# tube-inner_sch-pcb.net
KiCad netlist of a schematic drawn in EAGLE
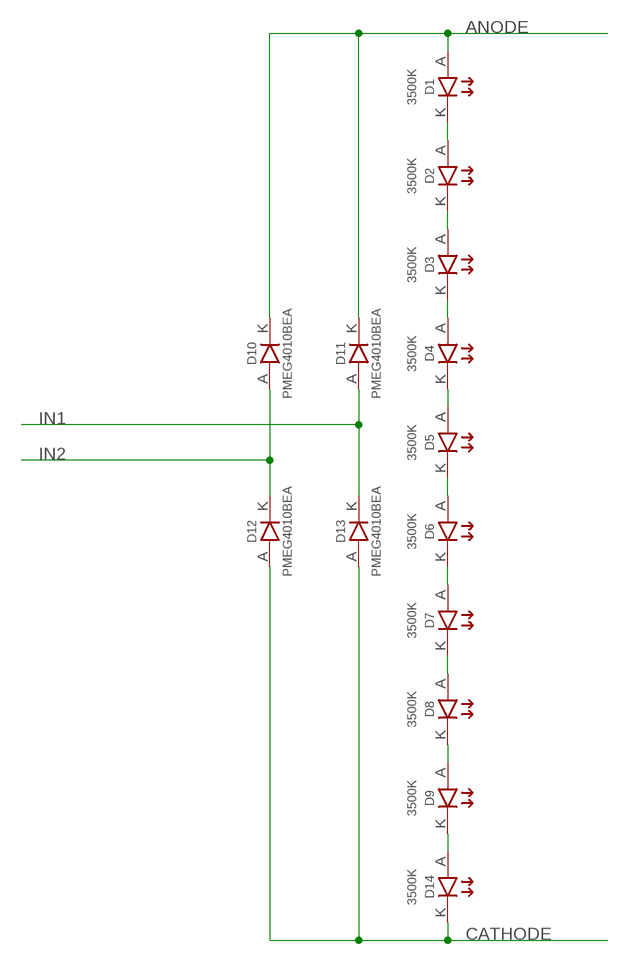
[diagram p0: schematic, sheet 1]

(export (version "E")
  (design (tool "Eeschema 10.0.6"))
  (components
    (comp (ref "D1")
      (value "3500K")
      (footprint "eagle-import:JE2835AWT")
      (libsource (lib "eagle-import") (part "JE2835AWT-00-0000-0B0A0UF735E"))
    )
    (comp (ref "D2")
      (value "3500K")
      (footprint "eagle-import:JE2835AWT")
      (libsource (lib "eagle-import") (part "JE2835AWT-00-0000-0B0A0UF735E"))
    )
    (comp (ref "D3")
      (value "3500K")
      (footprint "eagle-import:JE2835AWT")
      (libsource (lib "eagle-import") (part "JE2835AWT-00-0000-0B0A0UF735E"))
    )
    (comp (ref "D4")
      (value "3500K")
      (footprint "eagle-import:JE2835AWT")
      (libsource (lib "eagle-import") (part "JE2835AWT-00-0000-0B0A0UF735E"))
    )
    (comp (ref "D5")
      (value "3500K")
      (footprint "eagle-import:JE2835AWT")
      (libsource (lib "eagle-import") (part "JE2835AWT-00-0000-0B0A0UF735E"))
    )
    (comp (ref "D6")
      (value "3500K")
      (footprint "eagle-import:JE2835AWT")
      (libsource (lib "eagle-import") (part "JE2835AWT-00-0000-0B0A0UF735E"))
    )
    (comp (ref "D7")
      (value "3500K")
      (footprint "eagle-import:JE2835AWT")
      (libsource (lib "eagle-import") (part "JE2835AWT-00-0000-0B0A0UF735E"))
    )
    (comp (ref "D8")
      (value "3500K")
      (footprint "eagle-import:JE2835AWT")
      (libsource (lib "eagle-import") (part "JE2835AWT-00-0000-0B0A0UF735E"))
    )
    (comp (ref "D9")
      (value "3500K")
      (footprint "eagle-import:JE2835AWT")
      (libsource (lib "eagle-import") (part "JE2835AWT-00-0000-0B0A0UF735E"))
    )
    (comp (ref "D10")
      (value "PMEG4010BEA")
      (footprint "eagle-import:SOD-323")
      (libsource (lib "eagle-import") (part "PMEG4010BEA"))
    )
    (comp (ref "D11")
      (value "PMEG4010BEA")
      (footprint "eagle-import:SOD-323")
      (libsource (lib "eagle-import") (part "PMEG4010BEA"))
    )
    (comp (ref "D12")
      (value "PMEG4010BEA")
      (footprint "eagle-import:SOD-323")
      (libsource (lib "eagle-import") (part "PMEG4010BEA"))
    )
    (comp (ref "D13")
      (value "PMEG4010BEA")
      (footprint "eagle-import:SOD-323")
      (libsource (lib "eagle-import") (part "PMEG4010BEA"))
    )
    (comp (ref "D14")
      (value "3500K")
      (footprint "eagle-import:JE2835AWT")
      (libsource (lib "eagle-import") (part "JE2835AWT-00-0000-0B0A0UF735E"))
    )
  )
  (nets
    (net (code "1") (name "/ANODE") (class "Default")
      (node (ref "D1") (pin "A") (pinfunction "A_A") (pintype "bidirectional"))
      (node (ref "D10") (pin "K") (pinfunction "K_K") (pintype "bidirectional"))
      (node (ref "D11") (pin "K") (pinfunction "K_K") (pintype "bidirectional"))
    )
    (net (code "2") (name "/CATHODE") (class "Default")
      (node (ref "D12") (pin "A") (pinfunction "A_A") (pintype "bidirectional"))
      (node (ref "D13") (pin "A") (pinfunction "A_A") (pintype "bidirectional"))
      (node (ref "D14") (pin "K") (pinfunction "K_K") (pintype "bidirectional"))
    )
    (net (code "3") (name "/IN1") (class "Default")
      (node (ref "D11") (pin "A") (pinfunction "A_A") (pintype "bidirectional"))
      (node (ref "D13") (pin "K") (pinfunction "K_K") (pintype "bidirectional"))
    )
    (net (code "4") (name "/IN2") (class "Default")
      (node (ref "D10") (pin "A") (pinfunction "A_A") (pintype "bidirectional"))
      (node (ref "D12") (pin "K") (pinfunction "K_K") (pintype "bidirectional"))
    )
    (net (code "5") (name "Net-(D1-PadK)") (class "Default")
      (node (ref "D1") (pin "K") (pinfunction "K_K") (pintype "bidirectional"))
      (node (ref "D2") (pin "A") (pinfunction "A_A") (pintype "bidirectional"))
    )
    (net (code "6") (name "Net-(D2-PadK)") (class "Default")
      (node (ref "D2") (pin "K") (pinfunction "K_K") (pintype "bidirectional"))
      (node (ref "D3") (pin "A") (pinfunction "A_A") (pintype "bidirectional"))
    )
    (net (code "7") (name "Net-(D3-PadK)") (class "Default")
      (node (ref "D3") (pin "K") (pinfunction "K_K") (pintype "bidirectional"))
      (node (ref "D4") (pin "A") (pinfunction "A_A") (pintype "bidirectional"))
    )
    (net (code "8") (name "Net-(D4-PadK)") (class "Default")
      (node (ref "D4") (pin "K") (pinfunction "K_K") (pintype "bidirectional"))
      (node (ref "D5") (pin "A") (pinfunction "A_A") (pintype "bidirectional"))
    )
    (net (code "9") (name "Net-(D5-PadK)") (class "Default")
      (node (ref "D5") (pin "K") (pinfunction "K_K") (pintype "bidirectional"))
      (node (ref "D6") (pin "A") (pinfunction "A_A") (pintype "bidirectional"))
    )
    (net (code "10") (name "Net-(D6-PadK)") (class "Default")
      (node (ref "D6") (pin "K") (pinfunction "K_K") (pintype "bidirectional"))
      (node (ref "D7") (pin "A") (pinfunction "A_A") (pintype "bidirectional"))
    )
    (net (code "11") (name "Net-(D7-PadK)") (class "Default")
      (node (ref "D7") (pin "K") (pinfunction "K_K") (pintype "bidirectional"))
      (node (ref "D8") (pin "A") (pinfunction "A_A") (pintype "bidirectional"))
    )
    (net (code "12") (name "Net-(D8-PadK)") (class "Default")
      (node (ref "D8") (pin "K") (pinfunction "K_K") (pintype "bidirectional"))
      (node (ref "D9") (pin "A") (pinfunction "A_A") (pintype "bidirectional"))
    )
    (net (code "13") (name "Net-(D14-PadA)") (class "Default")
      (node (ref "D14") (pin "A") (pinfunction "A_A") (pintype "bidirectional"))
      (node (ref "D9") (pin "K") (pinfunction "K_K") (pintype "bidirectional"))
    )
  )
)
